# design.net
KiCad netlist of a schematic drawn in Altium Designer
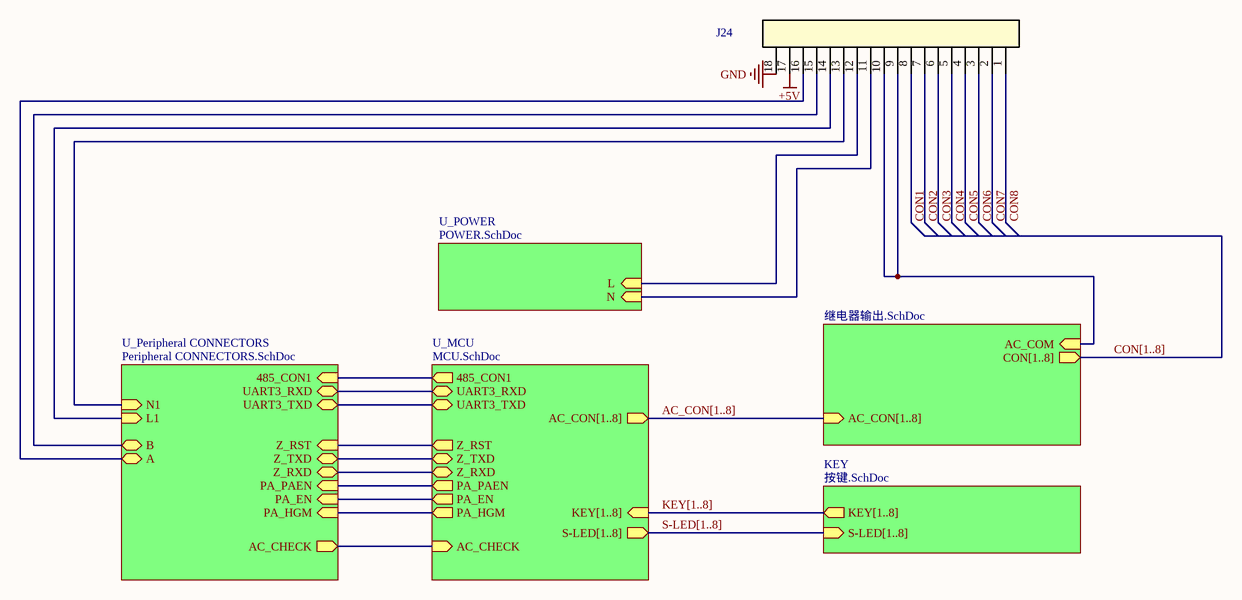
[diagram p0: 总图.SchDoc]

(export (version "E")
  (design (tool "Eeschema 10.0.6"))
  (components
    (comp (ref "J24")
      (value "KF2EDGK5.08-18P")
      (footprint "KF2EDGKG5.08-18P")
      (description "KF2EDGK5.08")
      (libsource (lib "接口") (part "KF2EDGK5.08-18P"))
    )
  )
  (nets
    (net (code "25") (name "+5V") (class "Default")
      (node (ref "J24") (pin "17") (pinfunction "17_17") (pintype "passive"))
    )
    (net (code "27") (name "/A") (class "Default")
      (node (ref "J24") (pin "16") (pinfunction "16_16") (pintype "passive"))
    )
    (net (code "29") (name "/AC_COM") (class "Default")
      (node (ref "J24") (pin "10") (pinfunction "10_10") (pintype "passive"))
      (node (ref "J24") (pin "9") (pinfunction "9_9") (pintype "passive"))
    )
    (net (code "31") (name "/B") (class "Default")
      (node (ref "J24") (pin "15") (pinfunction "15_15") (pintype "passive"))
    )
    (net (code "32") (name "/CON1") (class "Default")
      (node (ref "J24") (pin "8") (pinfunction "8_8") (pintype "passive"))
    )
    (net (code "33") (name "/CON2") (class "Default")
      (node (ref "J24") (pin "7") (pinfunction "7_7") (pintype "passive"))
    )
    (net (code "34") (name "/CON3") (class "Default")
      (node (ref "J24") (pin "6") (pinfunction "6_6") (pintype "passive"))
    )
    (net (code "35") (name "/CON4") (class "Default")
      (node (ref "J24") (pin "5") (pinfunction "5_5") (pintype "passive"))
    )
    (net (code "36") (name "/CON5") (class "Default")
      (node (ref "J24") (pin "4") (pinfunction "4_4") (pintype "passive"))
    )
    (net (code "37") (name "/CON6") (class "Default")
      (node (ref "J24") (pin "3") (pinfunction "3_3") (pintype "passive"))
    )
    (net (code "38") (name "/CON7") (class "Default")
      (node (ref "J24") (pin "2") (pinfunction "2_2") (pintype "passive"))
    )
    (net (code "39") (name "/CON8") (class "Default")
      (node (ref "J24") (pin "1") (pinfunction "1_1") (pintype "passive"))
    )
    (net (code "42") (name "/L") (class "Default")
      (node (ref "J24") (pin "12") (pinfunction "12_12") (pintype "passive"))
    )
    (net (code "43") (name "/L1") (class "Default")
      (node (ref "J24") (pin "14") (pinfunction "14_14") (pintype "passive"))
    )
    (net (code "44") (name "/N") (class "Default")
      (node (ref "J24") (pin "11") (pinfunction "11_11") (pintype "passive"))
    )
    (net (code "45") (name "/N1") (class "Default")
      (node (ref "J24") (pin "13") (pinfunction "13_13") (pintype "passive"))
    )
    (net (code "55") (name "GND") (class "Default")
      (node (ref "J24") (pin "18") (pinfunction "18_18") (pintype "passive"))
    )
  )
)
